# Acquisition_module.net
KiCad netlist of a schematic drawn in Altium Designer
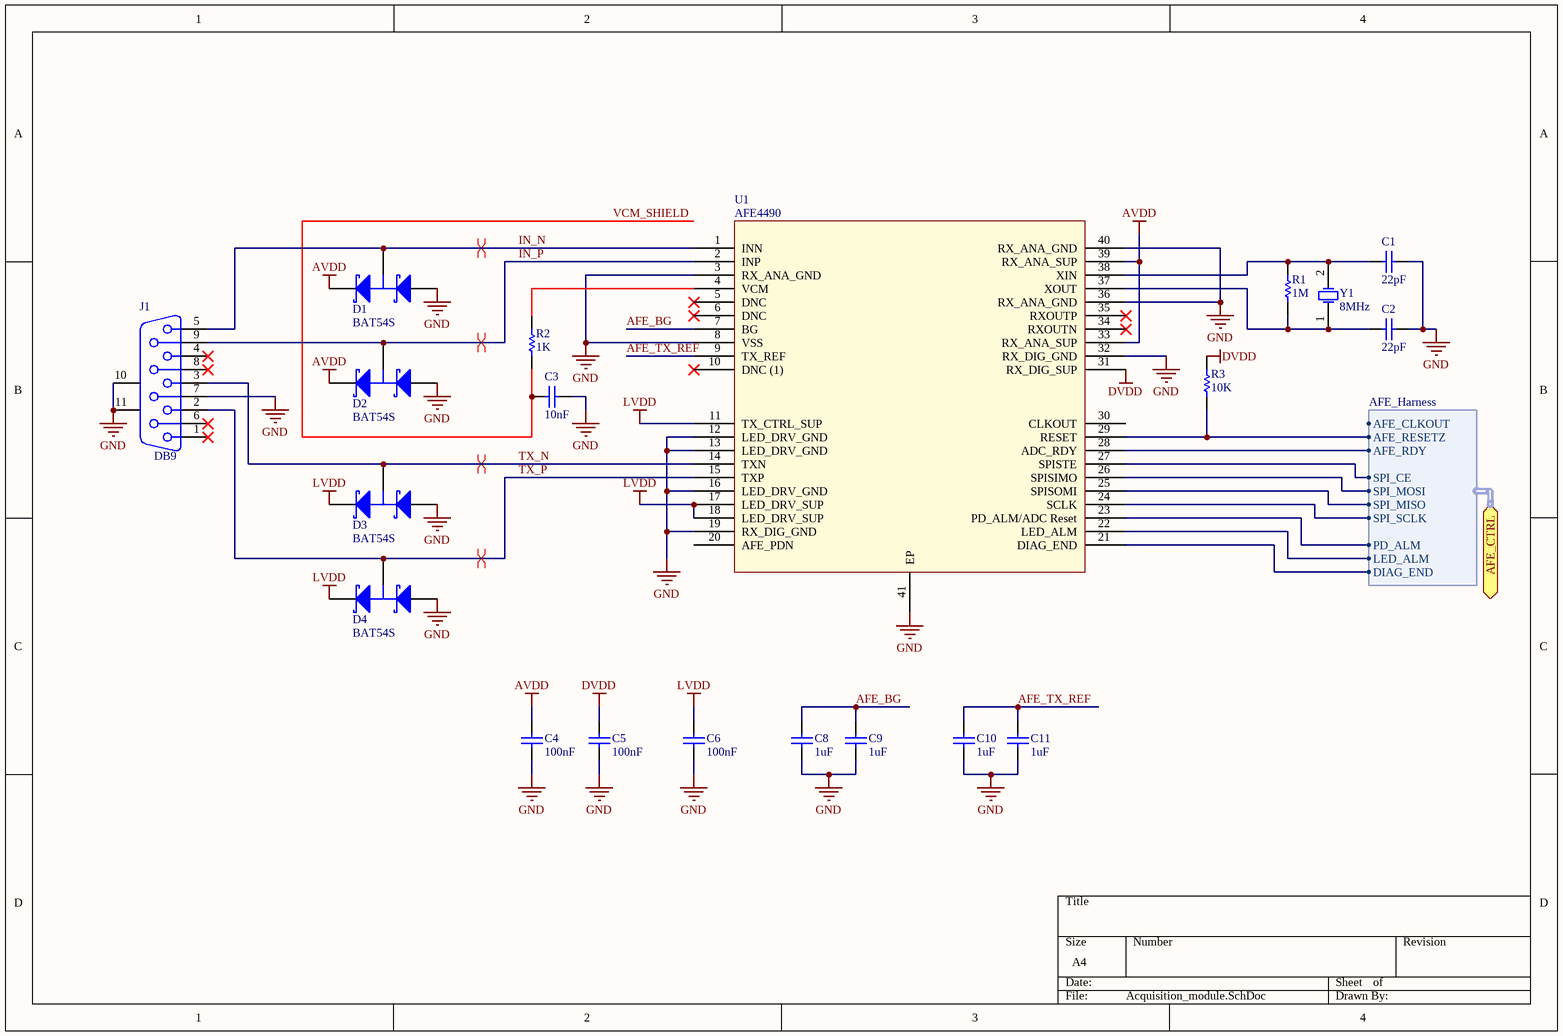
[diagram p0: Acquisition_module.SchDoc]

(export (version "E")
  (design (tool "Eeschema 10.0.6"))
  (components
    (comp (ref "C1")
      (value "22pF")
      (footprint "6-0805_M")
      (description "Capacitor")
      (fields (field (name "Comment") "Cap") (field (name "PUBLISHER") "Altium Limited"))
      (libsource (lib "Miscellaneous Devices") (part "Cap"))
    )
    (comp (ref "C2")
      (value "22pF")
      (footprint "6-0805_M")
      (description "Capacitor")
      (fields (field (name "Comment") "Cap") (field (name "PUBLISHER") "Altium Limited"))
      (libsource (lib "Miscellaneous Devices") (part "Cap"))
    )
    (comp (ref "C3")
      (value "10nF")
      (footprint "6-0805_M")
      (description "Capacitor")
      (fields (field (name "Comment") "Cap") (field (name "PUBLISHER") "Altium Limited"))
      (libsource (lib "Miscellaneous Devices") (part "Cap"))
    )
    (comp (ref "C4")
      (value "100nF")
      (footprint "6-0805_M")
      (description "Capacitor")
      (fields (field (name "Comment") "Cap") (field (name "PUBLISHER") "Altium Limited"))
      (libsource (lib "Miscellaneous Devices") (part "Cap"))
    )
    (comp (ref "C5")
      (value "100nF")
      (footprint "6-0805_M")
      (description "Capacitor")
      (fields (field (name "Comment") "Cap") (field (name "PUBLISHER") "Altium Limited"))
      (libsource (lib "Miscellaneous Devices") (part "Cap"))
    )
    (comp (ref "C6")
      (value "100nF")
      (footprint "6-0805_M")
      (description "Capacitor")
      (fields (field (name "Comment") "Cap") (field (name "PUBLISHER") "Altium Limited"))
      (libsource (lib "Miscellaneous Devices") (part "Cap"))
    )
    (comp (ref "C8")
      (value "1uF")
      (footprint "6-0805_M")
      (description "Capacitor")
      (fields (field (name "Comment") "Cap") (field (name "PUBLISHER") "Altium Limited"))
      (libsource (lib "Miscellaneous Devices") (part "Cap"))
    )
    (comp (ref "C9")
      (value "1uF")
      (footprint "6-0805_M")
      (description "Capacitor")
      (fields (field (name "Comment") "Cap") (field (name "PUBLISHER") "Altium Limited"))
      (libsource (lib "Miscellaneous Devices") (part "Cap"))
    )
    (comp (ref "C10")
      (value "1uF")
      (footprint "6-0805_M")
      (description "Capacitor")
      (fields (field (name "Comment") "Cap") (field (name "PUBLISHER") "Altium Limited"))
      (libsource (lib "Miscellaneous Devices") (part "Cap"))
    )
    (comp (ref "C11")
      (value "1uF")
      (footprint "6-0805_M")
      (description "Capacitor")
      (fields (field (name "Comment") "Cap") (field (name "PUBLISHER") "Altium Limited"))
      (libsource (lib "Miscellaneous Devices") (part "Cap"))
    )
    (comp (ref "D1")
      (value "BAT54S")
      (footprint "SOT23_N")
      (description "Schottky Barrier Double Diode")
      (fields (field (name "PUBLISHER") "Altium Limited"))
      (libsource (lib "Philips Discrete Diode - Schottky") (part "BAT54S"))
    )
    (comp (ref "D2")
      (value "BAT54S")
      (footprint "SOT23_N")
      (description "Schottky Barrier Double Diode")
      (fields (field (name "PUBLISHER") "Altium Limited"))
      (libsource (lib "Philips Discrete Diode - Schottky") (part "BAT54S"))
    )
    (comp (ref "D3")
      (value "BAT54S")
      (footprint "SOT23_N")
      (description "Schottky Barrier Double Diode")
      (fields (field (name "PUBLISHER") "Altium Limited"))
      (libsource (lib "Philips Discrete Diode - Schottky") (part "BAT54S"))
    )
    (comp (ref "D4")
      (value "BAT54S")
      (footprint "SOT23_N")
      (description "Schottky Barrier Double Diode")
      (fields (field (name "PUBLISHER") "Altium Limited"))
      (libsource (lib "Philips Discrete Diode - Schottky") (part "BAT54S"))
    )
    (comp (ref "J1")
      (value "DB9")
      (footprint "DB9")
      (description "Receptacle Assembly, 9 Position, Right Angle")
      (fields (field (name "PUBLISHER") "Altium Limited"))
      (libsource (lib "Miscellaneous Connectors") (part "D Connector 9"))
    )
    (comp (ref "R1")
      (value "1M")
      (footprint "6-0805_M")
      (description "Resistor")
      (fields (field (name "Comment") "Res1") (field (name "PUBLISHER") "Altium Limited"))
      (libsource (lib "Miscellaneous Devices") (part "Res1"))
    )
    (comp (ref "R2")
      (value "1K")
      (footprint "6-0805_M")
      (description "Resistor")
      (fields (field (name "Comment") "Res1") (field (name "PUBLISHER") "Altium Limited"))
      (libsource (lib "Miscellaneous Devices") (part "Res1"))
    )
    (comp (ref "R3")
      (value "10K")
      (footprint "6-0805_M")
      (description "Resistor")
      (fields (field (name "Comment") "Res1") (field (name "PUBLISHER") "Altium Limited"))
      (libsource (lib "Miscellaneous Devices") (part "Res1"))
    )
    (comp (ref "U1")
      (value "AFE4490")
      (footprint "AFE4490QFN50P680X680X100_HS-41N")
      (description "Integrated Analog Front-End for Pulse Oximeters")
      (libsource (lib "AFE4490") (part "AFE4490"))
    )
    (comp (ref "Y1")
      (value "8MHz")
      (footprint "Crystal SMD")
      (description "Crystal Oscillator")
      (fields (field (name "PUBLISHER") "Altium Limited"))
      (libsource (lib "Miscellaneous Devices") (part "XTAL"))
    )
  )
  (nets
    (net (code "2") (name "/AFE_BG") (class "Default")
      (node (ref "C8") (pin "2") (pinfunction "2_2") (pintype "passive"))
      (node (ref "C9") (pin "2") (pinfunction "2_2") (pintype "passive"))
      (node (ref "U1") (pin "7") (pinfunction "BG_7") (pintype "passive"))
    )
    (net (code "3") (name "/AFE_RDY") (class "Default")
      (node (ref "U1") (pin "28") (pinfunction "ADC_RDY_28") (pintype "passive"))
    )
    (net (code "4") (name "/AFE_RESETZ") (class "Default")
      (node (ref "R3") (pin "1") (pinfunction "1_1") (pintype "passive"))
      (node (ref "U1") (pin "29") (pinfunction "RESET_29") (pintype "passive"))
    )
    (net (code "5") (name "/AFE_TX_REF") (class "Default")
      (node (ref "C10") (pin "2") (pinfunction "2_2") (pintype "passive"))
      (node (ref "C11") (pin "2") (pinfunction "2_2") (pintype "passive"))
      (node (ref "U1") (pin "9") (pinfunction "TX_REF_9") (pintype "passive"))
    )
    (net (code "6") (name "/DIAG_END") (class "Default")
      (node (ref "U1") (pin "21") (pinfunction "DIAG_END_21") (pintype "passive"))
    )
    (net (code "7") (name "/IN_N") (class "Default")
      (node (ref "D1") (pin "3") (pinfunction "C_3") (pintype "passive"))
      (node (ref "J1") (pin "5") (pinfunction "5_5") (pintype "passive"))
      (node (ref "U1") (pin "1") (pinfunction "INN_1") (pintype "passive"))
    )
    (net (code "8") (name "/IN_P") (class "Default")
      (node (ref "D2") (pin "3") (pinfunction "C_3") (pintype "passive"))
      (node (ref "J1") (pin "9") (pinfunction "9_9") (pintype "passive"))
      (node (ref "U1") (pin "2") (pinfunction "INP_2") (pintype "passive"))
    )
    (net (code "9") (name "/LED_ALM") (class "Default")
      (node (ref "U1") (pin "22") (pinfunction "LED_ALM_22") (pintype "passive"))
    )
    (net (code "10") (name "/PD_ALM") (class "Default")
      (node (ref "U1") (pin "23") (pinfunction "PD_ALM/ADC_Reset_23") (pintype "passive"))
    )
    (net (code "11") (name "/SPI_CE") (class "Default")
      (node (ref "U1") (pin "27") (pinfunction "SPISTE_27") (pintype "passive"))
    )
    (net (code "12") (name "/SPI_MISO") (class "Default")
      (node (ref "U1") (pin "25") (pinfunction "SPISOMI_25") (pintype "passive"))
    )
    (net (code "13") (name "/SPI_MOSI") (class "Default")
      (node (ref "U1") (pin "26") (pinfunction "SPISIMO_26") (pintype "passive"))
    )
    (net (code "14") (name "/SPI_SCLK") (class "Default")
      (node (ref "U1") (pin "24") (pinfunction "SCLK_24") (pintype "passive"))
    )
    (net (code "15") (name "/TX_N") (class "Default")
      (node (ref "D3") (pin "3") (pinfunction "C_3") (pintype "passive"))
      (node (ref "J1") (pin "3") (pinfunction "3_3") (pintype "passive"))
      (node (ref "U1") (pin "14") (pinfunction "TXN_14") (pintype "passive"))
    )
    (net (code "16") (name "/TX_P") (class "Default")
      (node (ref "D4") (pin "3") (pinfunction "C_3") (pintype "passive"))
      (node (ref "J1") (pin "2") (pinfunction "2_2") (pintype "passive"))
      (node (ref "U1") (pin "15") (pinfunction "TXP_15") (pintype "passive"))
    )
    (net (code "17") (name "/VCM_SHIELD") (class "Default")
      (node (ref "C3") (pin "2") (pinfunction "2_2") (pintype "passive"))
      (node (ref "R2") (pin "1") (pinfunction "1_1") (pintype "passive"))
    )
    (net (code "19") (name "AVDD") (class "Default")
      (node (ref "C4") (pin "2") (pinfunction "2_2") (pintype "passive"))
      (node (ref "D1") (pin "2") (pinfunction "K_2") (pintype "passive"))
      (node (ref "D2") (pin "2") (pinfunction "K_2") (pintype "passive"))
      (node (ref "U1") (pin "33") (pinfunction "RX_ANA_SUP_33") (pintype "passive"))
      (node (ref "U1") (pin "39") (pinfunction "RX_ANA_SUP_39") (pintype "passive"))
    )
    (net (code "20") (name "DVDD") (class "Default")
      (node (ref "C5") (pin "2") (pinfunction "2_2") (pintype "passive"))
      (node (ref "R3") (pin "2") (pinfunction "2_2") (pintype "passive"))
      (node (ref "U1") (pin "31") (pinfunction "RX_DIG_SUP_31") (pintype "passive"))
    )
    (net (code "21") (name "GND") (class "Default")
      (node (ref "C1") (pin "1") (pinfunction "1_1") (pintype "passive"))
      (node (ref "C10") (pin "1") (pinfunction "1_1") (pintype "passive"))
      (node (ref "C11") (pin "1") (pinfunction "1_1") (pintype "passive"))
      (node (ref "C2") (pin "1") (pinfunction "1_1") (pintype "passive"))
      (node (ref "C3") (pin "1") (pinfunction "1_1") (pintype "passive"))
      (node (ref "C4") (pin "1") (pinfunction "1_1") (pintype "passive"))
      (node (ref "C5") (pin "1") (pinfunction "1_1") (pintype "passive"))
      (node (ref "C6") (pin "1") (pinfunction "1_1") (pintype "passive"))
      (node (ref "C8") (pin "1") (pinfunction "1_1") (pintype "passive"))
      (node (ref "C9") (pin "1") (pinfunction "1_1") (pintype "passive"))
      (node (ref "D1") (pin "1") (pinfunction "A_1") (pintype "passive"))
      (node (ref "D2") (pin "1") (pinfunction "A_1") (pintype "passive"))
      (node (ref "D3") (pin "1") (pinfunction "A_1") (pintype "passive"))
      (node (ref "D4") (pin "1") (pinfunction "A_1") (pintype "passive"))
      (node (ref "J1") (pin "10") (pinfunction "MH1_10") (pintype "passive"))
      (node (ref "J1") (pin "11") (pinfunction "MH2_11") (pintype "passive"))
      (node (ref "J1") (pin "7") (pinfunction "7_7") (pintype "passive"))
      (node (ref "U1") (pin "12") (pinfunction "LED_DRV_GND_12") (pintype "passive"))
      (node (ref "U1") (pin "13") (pinfunction "LED_DRV_GND_13") (pintype "passive"))
      (node (ref "U1") (pin "16") (pinfunction "LED_DRV_GND_16") (pintype "passive"))
      (node (ref "U1") (pin "19") (pinfunction "RX_DIG_GND_19") (pintype "passive"))
      (node (ref "U1") (pin "3") (pinfunction "RX_ANA_GND_3") (pintype "passive"))
      (node (ref "U1") (pin "32") (pinfunction "RX_DIG_GND_32") (pintype "passive"))
      (node (ref "U1") (pin "36") (pinfunction "RX_ANA_GND_36") (pintype "passive"))
      (node (ref "U1") (pin "40") (pinfunction "RX_ANA_GND_40") (pintype "passive"))
      (node (ref "U1") (pin "41") (pinfunction "EP_41") (pintype "passive"))
      (node (ref "U1") (pin "8") (pinfunction "VSS_8") (pintype "passive"))
    )
    (net (code "22") (name "LVDD") (class "Default")
      (node (ref "C6") (pin "2") (pinfunction "2_2") (pintype "passive"))
      (node (ref "D3") (pin "2") (pinfunction "K_2") (pintype "passive"))
      (node (ref "D4") (pin "2") (pinfunction "K_2") (pintype "passive"))
      (node (ref "U1") (pin "11") (pinfunction "TX_CTRL_SUP_11") (pintype "passive"))
      (node (ref "U1") (pin "17") (pinfunction "LED_DRV_SUP_17") (pintype "passive"))
      (node (ref "U1") (pin "18") (pinfunction "LED_DRV_SUP_18") (pintype "passive"))
    )
    (net (code "23") (name "Net-(U1-VCM)") (class "Default")
      (node (ref "R2") (pin "2") (pinfunction "2_2") (pintype "passive"))
      (node (ref "U1") (pin "4") (pinfunction "VCM_4") (pintype "passive"))
    )
    (net (code "24") (name "Net-(U1-XIN)") (class "Default")
      (node (ref "C1") (pin "2") (pinfunction "2_2") (pintype "passive"))
      (node (ref "R1") (pin "1") (pinfunction "1_1") (pintype "passive"))
      (node (ref "U1") (pin "38") (pinfunction "XIN_38") (pintype "passive"))
      (node (ref "Y1") (pin "2") (pinfunction "OSC2_2") (pintype "passive"))
    )
    (net (code "25") (name "Net-(U1-XOUT)") (class "Default")
      (node (ref "C2") (pin "2") (pinfunction "2_2") (pintype "passive"))
      (node (ref "R1") (pin "2") (pinfunction "2_2") (pintype "passive"))
      (node (ref "U1") (pin "37") (pinfunction "XOUT_37") (pintype "passive"))
      (node (ref "Y1") (pin "1") (pinfunction "OSC1_1") (pintype "passive"))
    )
    (net (code "26") (name "unconnected-(J1-Pad1)") (class "Default")
      (node (ref "J1") (pin "1") (pinfunction "1_1") (pintype "passive+no_connect"))
    )
    (net (code "27") (name "unconnected-(J1-Pad4)") (class "Default")
      (node (ref "J1") (pin "4") (pinfunction "4_4") (pintype "passive+no_connect"))
    )
    (net (code "28") (name "unconnected-(J1-Pad6)") (class "Default")
      (node (ref "J1") (pin "6") (pinfunction "6_6") (pintype "passive+no_connect"))
    )
    (net (code "29") (name "unconnected-(J1-Pad8)") (class "Default")
      (node (ref "J1") (pin "8") (pinfunction "8_8") (pintype "passive+no_connect"))
    )
    (net (code "30") (name "unconnected-(U1-AFE_PDN-Pad20)") (class "Default")
      (node (ref "U1") (pin "20") (pinfunction "AFE_PDN_20") (pintype "passive"))
    )
    (net (code "31") (name "unconnected-(U1-CLKOUT-Pad30)") (class "Default")
      (node (ref "U1") (pin "30") (pinfunction "CLKOUT_30") (pintype "passive"))
    )
    (net (code "32") (name "unconnected-(U1-DNC-Pad5)") (class "Default")
      (node (ref "U1") (pin "5") (pinfunction "DNC_5") (pintype "passive+no_connect"))
    )
    (net (code "33") (name "unconnected-(U1-DNC-Pad6)") (class "Default")
      (node (ref "U1") (pin "6") (pinfunction "DNC_6") (pintype "passive+no_connect"))
    )
    (net (code "34") (name "unconnected-(U1-DNC_(1)-Pad10)") (class "Default")
      (node (ref "U1") (pin "10") (pinfunction "DNC_(1)_10") (pintype "passive+no_connect"))
    )
    (net (code "35") (name "unconnected-(U1-RXOUTN-Pad34)") (class "Default")
      (node (ref "U1") (pin "34") (pinfunction "RXOUTN_34") (pintype "passive+no_connect"))
    )
    (net (code "36") (name "unconnected-(U1-RXOUTP-Pad35)") (class "Default")
      (node (ref "U1") (pin "35") (pinfunction "RXOUTP_35") (pintype "passive+no_connect"))
    )
  )
)
